# RefOsc10MHz_1V0.net
KiCad netlist of a schematic drawn in EAGLE
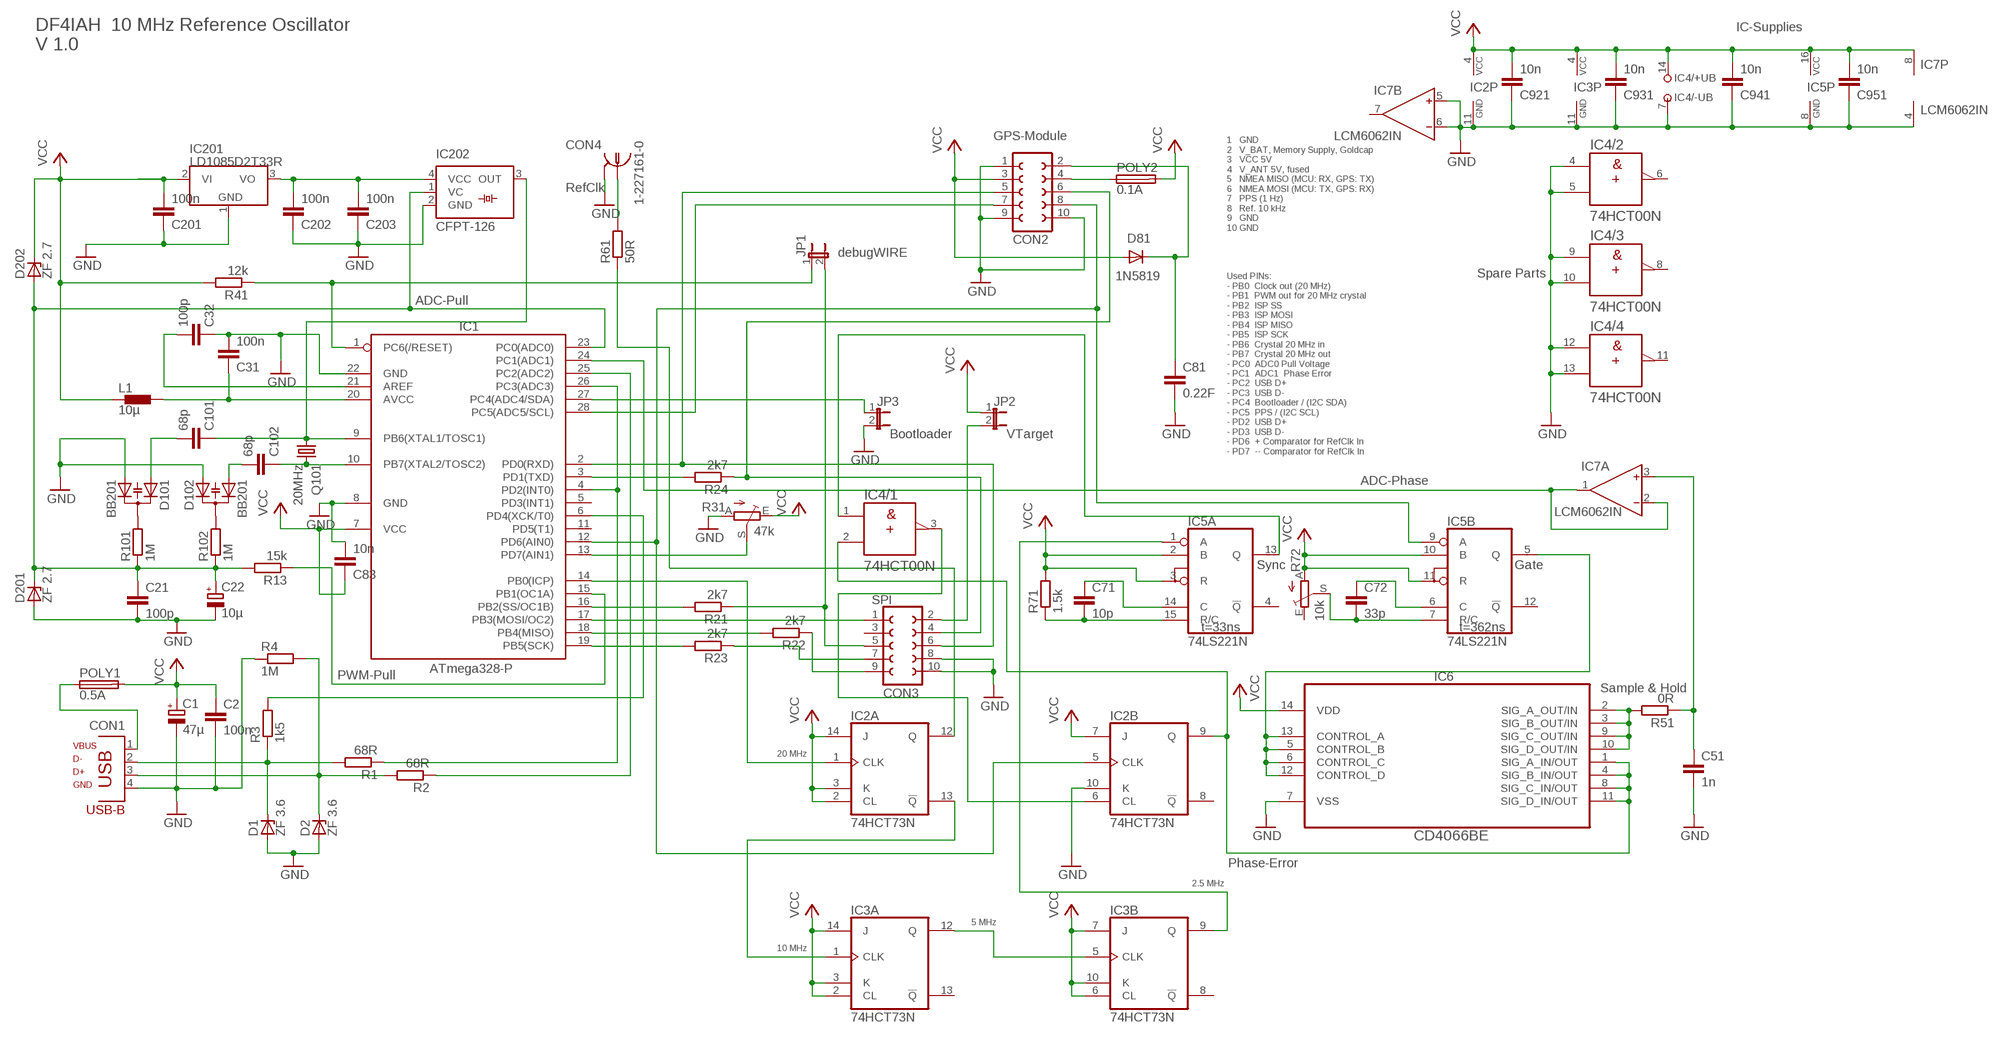
[diagram p0: schematic, sheet 1]

(export (version "E")
  (design (tool "Eeschema 10.0.6"))
  (components
    (comp (ref "C1")
      (value "47µ")
      (footprint "eagle-import:E2-4")
      (libsource (lib "eagle-import") (part "CPOL-EUE2-4"))
    )
    (comp (ref "C2")
      (value "100n")
      (footprint "eagle-import:C5B3")
      (libsource (lib "eagle-import") (part "C5/3"))
    )
    (comp (ref "C21")
      (value "100p")
      (footprint "eagle-import:C5B3")
      (libsource (lib "eagle-import") (part "C5/3"))
    )
    (comp (ref "C22")
      (value "10µ")
      (footprint "eagle-import:E2-4")
      (libsource (lib "eagle-import") (part "CPOL-EUE2-4"))
    )
    (comp (ref "C31")
      (value "100n")
      (footprint "eagle-import:C5B3")
      (libsource (lib "eagle-import") (part "C5/3"))
    )
    (comp (ref "C32")
      (value "100p")
      (footprint "eagle-import:C5B3")
      (libsource (lib "eagle-import") (part "C5/3"))
    )
    (comp (ref "C51")
      (value "1n")
      (footprint "eagle-import:C5B3")
      (libsource (lib "eagle-import") (part "C5/3"))
    )
    (comp (ref "C71")
      (value "10p")
      (footprint "eagle-import:C5B3")
      (libsource (lib "eagle-import") (part "C5/3"))
    )
    (comp (ref "C72")
      (value "33p")
      (footprint "eagle-import:C5B3")
      (libsource (lib "eagle-import") (part "C5/3"))
    )
    (comp (ref "C81")
      (value "0.22F")
      (footprint "eagle-import:C5B7.2")
      (libsource (lib "eagle-import") (part "C5/7.2"))
    )
    (comp (ref "C83")
      (value "10n")
      (footprint "eagle-import:C5B3")
      (libsource (lib "eagle-import") (part "C5/3"))
    )
    (comp (ref "C101")
      (value "68p")
      (footprint "eagle-import:C5B3")
      (libsource (lib "eagle-import") (part "C5/3"))
    )
    (comp (ref "C102")
      (value "68p")
      (footprint "eagle-import:C5B3")
      (libsource (lib "eagle-import") (part "C5/3"))
    )
    (comp (ref "C201")
      (value "100n")
      (footprint "eagle-import:C5B3")
      (libsource (lib "eagle-import") (part "C5/3"))
    )
    (comp (ref "C202")
      (value "100n")
      (footprint "eagle-import:C5B3")
      (libsource (lib "eagle-import") (part "C5/3"))
    )
    (comp (ref "C203")
      (value "100n")
      (footprint "eagle-import:C5B3")
      (libsource (lib "eagle-import") (part "C5/3"))
    )
    (comp (ref "C921")
      (value "10n")
      (footprint "eagle-import:C5B3")
      (libsource (lib "eagle-import") (part "C5/3"))
    )
    (comp (ref "C931")
      (value "10n")
      (footprint "eagle-import:C5B3")
      (libsource (lib "eagle-import") (part "C5/3"))
    )
    (comp (ref "C941")
      (value "10n")
      (footprint "eagle-import:C5B3")
      (libsource (lib "eagle-import") (part "C5/3"))
    )
    (comp (ref "C951")
      (value "10n")
      (footprint "eagle-import:C5B3")
      (libsource (lib "eagle-import") (part "C5/3"))
    )
    (comp (ref "CON1")
      (value "PN61729")
      (footprint "eagle-import:PN61729")
      (libsource (lib "eagle-import") (part "PN61729"))
    )
    (comp (ref "CON2")
      (value "FE05-2")
      (footprint "eagle-import:FE05-2")
      (libsource (lib "eagle-import") (part "FE05-2"))
    )
    (comp (ref "CON3")
      (value "FE05-2")
      (footprint "eagle-import:FE05-2")
      (libsource (lib "eagle-import") (part "FE05-2"))
    )
    (comp (ref "CON4")
      (value "1-227161-0")
      (footprint "eagle-import:AMP_227161")
      (fields (field (name "MF") "TYCO ELECTRONICS") (field (name "MPN") "1-227161"))
      (libsource (lib "eagle-import") (part "?2271611--0"))
    )
    (comp (ref "D1")
      (value "ZF 3.6")
      (footprint "eagle-import:DO41Z10")
      (libsource (lib "eagle-import") (part "1N4728"))
    )
    (comp (ref "D2")
      (value "ZF 3.6")
      (footprint "eagle-import:DO41Z10")
      (libsource (lib "eagle-import") (part "1N4728"))
    )
    (comp (ref "D81")
      (value "1N5819")
      (footprint "eagle-import:DO41-10")
      (libsource (lib "eagle-import") (part "1N4942"))
    )
    (comp (ref "D101")
      (value "BB201")
      (footprint "eagle-import:SOT23")
      (libsource (lib "eagle-import") (part "BBY51"))
    )
    (comp (ref "D102")
      (value "BB201")
      (footprint "eagle-import:SOT23")
      (libsource (lib "eagle-import") (part "BBY51"))
    )
    (comp (ref "D201")
      (value "ZF 2.7")
      (footprint "eagle-import:DO41Z10")
      (libsource (lib "eagle-import") (part "1N4728"))
    )
    (comp (ref "D202")
      (value "ZF 2.7")
      (footprint "eagle-import:DO41Z10")
      (libsource (lib "eagle-import") (part "1N4728"))
    )
    (comp (ref "IC1")
      (value "ATmega328-P")
      (footprint "eagle-import:DIL28-3")
      (libsource (lib "eagle-import") (part "MEGA8-P"))
    )
    (comp (ref "IC2")
      (value "74HCT73N")
      (footprint "eagle-import:DIL14")
      (libsource (lib "eagle-import") (part "7473NLS"))
    )
    (comp (ref "IC3")
      (value "74HCT73N")
      (footprint "eagle-import:DIL14")
      (libsource (lib "eagle-import") (part "7473NLS"))
    )
    (comp (ref "IC4")
      (value "74HCT00N")
      (footprint "eagle-import:DIL14")
      (libsource (lib "eagle-import") (part "7400NHCT"))
    )
    (comp (ref "IC5")
      (value "74LS221N")
      (footprint "eagle-import:DIL16")
      (libsource (lib "eagle-import") (part "74221NLS"))
    )
    (comp (ref "IC6")
      (value "CD4066BE")
      (footprint "eagle-import:DIP254P762X508-14")
      (libsource (lib "eagle-import") (part "CD4066BE"))
    )
    (comp (ref "IC7")
      (value "LCM6062IN")
      (footprint "eagle-import:DIL08")
      (libsource (lib "eagle-import") (part "AD822IN"))
    )
    (comp (ref "IC201")
      (value "LD10853.3")
      (footprint "eagle-import:TO220V")
      (libsource (lib "eagle-import") (part "LD10853.3"))
    )
    (comp (ref "IC202")
      (value "CFPT-126")
      (footprint "eagle-import:SM77H")
      (libsource (lib "eagle-import") (part "CFPT-126"))
    )
    (comp (ref "JP1")
      (value "JP1E")
      (footprint "eagle-import:JP1")
      (libsource (lib "eagle-import") (part "JP1E"))
    )
    (comp (ref "JP2")
      (value "JP1E")
      (footprint "eagle-import:JP1")
      (libsource (lib "eagle-import") (part "JP1E"))
    )
    (comp (ref "JP3")
      (value "JP1E")
      (footprint "eagle-import:JP1")
      (libsource (lib "eagle-import") (part "JP1E"))
    )
    (comp (ref "L1")
      (value "10µ")
      (footprint "eagle-import:BL01RN1A")
      (libsource (lib "eagle-import") (part "BL01RN1A"))
    )
    (comp (ref "POLY1")
      (value "0.5A")
      (footprint "eagle-import:TE5")
      (libsource (lib "eagle-import") (part "FUSETE5"))
    )
    (comp (ref "POLY2")
      (value "0.1A")
      (footprint "eagle-import:TE5")
      (libsource (lib "eagle-import") (part "FUSETE5"))
    )
    (comp (ref "Q101")
      (value "20MHz")
      (footprint "eagle-import:HC49U70")
      (libsource (lib "eagle-import") (part "CRYSTALHC49U70"))
    )
    (comp (ref "R1")
      (value "68R")
      (footprint "eagle-import:0204_7")
      (libsource (lib "eagle-import") (part "R-EU_0204/7"))
    )
    (comp (ref "R2")
      (value "68R")
      (footprint "eagle-import:0204_7")
      (libsource (lib "eagle-import") (part "R-EU_0204/7"))
    )
    (comp (ref "R3")
      (value "1k5")
      (footprint "eagle-import:0204_7")
      (libsource (lib "eagle-import") (part "R-EU_0204/7"))
    )
    (comp (ref "R4")
      (value "1M")
      (footprint "eagle-import:0204_7")
      (libsource (lib "eagle-import") (part "R-EU_0204/7"))
    )
    (comp (ref "R13")
      (value "15k")
      (footprint "eagle-import:0204_7")
      (libsource (lib "eagle-import") (part "R-EU_0204/7"))
    )
    (comp (ref "R21")
      (value "2k7")
      (footprint "eagle-import:0204_7")
      (libsource (lib "eagle-import") (part "R-EU_0204/7"))
    )
    (comp (ref "R22")
      (value "2k7")
      (footprint "eagle-import:0204_7")
      (libsource (lib "eagle-import") (part "R-EU_0204/7"))
    )
    (comp (ref "R23")
      (value "2k7")
      (footprint "eagle-import:0204_7")
      (libsource (lib "eagle-import") (part "R-EU_0204/7"))
    )
    (comp (ref "R24")
      (value "2k7")
      (footprint "eagle-import:0204_7")
      (libsource (lib "eagle-import") (part "R-EU_0204/7"))
    )
    (comp (ref "R31")
      (value "47k")
      (footprint "eagle-import:S64YW")
      (libsource (lib "eagle-import") (part "TRIM_1234-S64YW"))
    )
    (comp (ref "R41")
      (value "12k")
      (footprint "eagle-import:0204_7")
      (libsource (lib "eagle-import") (part "R-EU_0204/7"))
    )
    (comp (ref "R51")
      (value "0R")
      (footprint "eagle-import:0204_7")
      (libsource (lib "eagle-import") (part "R-EU_0204/7"))
    )
    (comp (ref "R61")
      (value "50R")
      (footprint "eagle-import:0204_7")
      (libsource (lib "eagle-import") (part "R-EU_0204/7"))
    )
    (comp (ref "R71")
      (value "1.5k")
      (footprint "eagle-import:0204_7")
      (libsource (lib "eagle-import") (part "R-EU_0204/7"))
    )
    (comp (ref "R72")
      (value "10k")
      (footprint "eagle-import:S64YW")
      (libsource (lib "eagle-import") (part "TRIM_1234-S64YW"))
    )
    (comp (ref "R101")
      (value "1M")
      (footprint "eagle-import:0204_7")
      (libsource (lib "eagle-import") (part "R-EU_0204/7"))
    )
    (comp (ref "R102")
      (value "1M")
      (footprint "eagle-import:0204_7")
      (libsource (lib "eagle-import") (part "R-EU_0204/7"))
    )
  )
  (nets
    (net (code "1") (name "GND") (class "Default")
      (node (ref "C1") (pin "-") (pinfunction "-_-") (pintype "passive"))
      (node (ref "C2") (pin "2") (pinfunction "2_2") (pintype "passive"))
      (node (ref "C201") (pin "1") (pinfunction "1_1") (pintype "passive"))
      (node (ref "C202") (pin "1") (pinfunction "1_1") (pintype "passive"))
      (node (ref "C203") (pin "1") (pinfunction "1_1") (pintype "passive"))
      (node (ref "C21") (pin "2") (pinfunction "2_2") (pintype "passive"))
      (node (ref "C22") (pin "-") (pinfunction "-_-") (pintype "passive"))
      (node (ref "C31") (pin "2") (pinfunction "2_2") (pintype "passive"))
      (node (ref "C32") (pin "1") (pinfunction "1_1") (pintype "passive"))
      (node (ref "C51") (pin "2") (pinfunction "2_2") (pintype "passive"))
      (node (ref "C81") (pin "2") (pinfunction "2_2") (pintype "passive"))
      (node (ref "C83") (pin "2") (pinfunction "2_2") (pintype "passive"))
      (node (ref "C921") (pin "1") (pinfunction "1_1") (pintype "passive"))
      (node (ref "C931") (pin "1") (pinfunction "1_1") (pintype "passive"))
      (node (ref "C941") (pin "1") (pinfunction "1_1") (pintype "passive"))
      (node (ref "C951") (pin "1") (pinfunction "1_1") (pintype "passive"))
      (node (ref "CON1") (pin "4") (pinfunction "4_4") (pintype "passive"))
      (node (ref "CON2") (pin "1") (pinfunction "1_1") (pintype "passive"))
      (node (ref "CON2") (pin "10") (pinfunction "10_10") (pintype "passive"))
      (node (ref "CON2") (pin "9") (pinfunction "9_9") (pintype "passive"))
      (node (ref "CON3") (pin "10") (pinfunction "10_10") (pintype "passive"))
      (node (ref "CON3") (pin "8") (pinfunction "8_8") (pintype "passive"))
      (node (ref "CON4") (pin "2") (pinfunction "2_2") (pintype "passive"))
      (node (ref "D1") (pin "A") (pinfunction "A_A") (pintype "passive"))
      (node (ref "D101") (pin "2") (pinfunction "A2_2") (pintype "passive"))
      (node (ref "D102") (pin "1") (pinfunction "A1_1") (pintype "passive"))
      (node (ref "D2") (pin "A") (pinfunction "A_A") (pintype "passive"))
      (node (ref "D201") (pin "A") (pinfunction "A_A") (pintype "passive"))
      (node (ref "IC1") (pin "22") (pinfunction "GND_22") (pintype "power_in"))
      (node (ref "IC1") (pin "8") (pinfunction "GND_8") (pintype "power_in"))
      (node (ref "IC2") (pin "10") (pinfunction "K_10") (pintype "input"))
      (node (ref "IC2") (pin "11") (pinfunction "GND_11") (pintype "power_in"))
      (node (ref "IC201") (pin "1") (pinfunction "GND_1") (pintype "passive"))
      (node (ref "IC202") (pin "2") (pinfunction "GND_2") (pintype "power_in"))
      (node (ref "IC3") (pin "11") (pinfunction "GND_11") (pintype "power_in"))
      (node (ref "IC4") (pin "10") (pinfunction "B_10") (pintype "input"))
      (node (ref "IC4") (pin "12") (pinfunction "A_12") (pintype "input"))
      (node (ref "IC4") (pin "13") (pinfunction "B_13") (pintype "input"))
      (node (ref "IC4") (pin "4") (pinfunction "A_4") (pintype "input"))
      (node (ref "IC4") (pin "5") (pinfunction "B_5") (pintype "input"))
      (node (ref "IC4") (pin "7") (pinfunction "-UB_7") (pintype "power_in"))
      (node (ref "IC4") (pin "9") (pinfunction "A_9") (pintype "input"))
      (node (ref "IC5") (pin "8") (pinfunction "GND_8") (pintype "power_in"))
      (node (ref "IC6") (pin "7") (pinfunction "VSS_7") (pintype "passive"))
      (node (ref "IC7") (pin "4") (pinfunction "V-_4") (pintype "power_in"))
      (node (ref "IC7") (pin "5") (pinfunction "IN+_5") (pintype "input"))
      (node (ref "IC7") (pin "6") (pinfunction "IN-_6") (pintype "input"))
      (node (ref "JP3") (pin "2") (pinfunction "2_2") (pintype "passive"))
      (node (ref "R31") (pin "A") (pinfunction "A_A") (pintype "passive"))
      (node (ref "R4") (pin "1") (pinfunction "1_1") (pintype "passive"))
    )
    (net (code "2") (name "Net-(C81-Pad1)") (class "Default")
      (node (ref "C81") (pin "1") (pinfunction "1_1") (pintype "passive"))
      (node (ref "CON2") (pin "2") (pinfunction "2_2") (pintype "passive"))
      (node (ref "D81") (pin "C") (pinfunction "C_C") (pintype "passive"))
    )
    (net (code "3") (name "Net-(CON1-Pad1)") (class "Default")
      (node (ref "CON1") (pin "1") (pinfunction "1_1") (pintype "passive"))
      (node (ref "POLY1") (pin "1") (pinfunction "1_1") (pintype "passive"))
    )
    (net (code "4") (name "Net-(CON1-Pad2)") (class "Default")
      (node (ref "CON1") (pin "2") (pinfunction "2_2") (pintype "passive"))
      (node (ref "D1") (pin "C") (pinfunction "C_C") (pintype "passive"))
      (node (ref "R1") (pin "2") (pinfunction "2_2") (pintype "passive"))
      (node (ref "R3") (pin "1") (pinfunction "1_1") (pintype "passive"))
    )
    (net (code "5") (name "Net-(CON1-Pad3)") (class "Default")
      (node (ref "CON1") (pin "3") (pinfunction "3_3") (pintype "passive"))
      (node (ref "D2") (pin "C") (pinfunction "C_C") (pintype "passive"))
      (node (ref "R2") (pin "2") (pinfunction "2_2") (pintype "passive"))
      (node (ref "R4") (pin "2") (pinfunction "2_2") (pintype "passive"))
    )
    (net (code "6") (name "Net-(CON2-Pad4)") (class "Default")
      (node (ref "CON2") (pin "4") (pinfunction "4_4") (pintype "passive"))
      (node (ref "POLY2") (pin "1") (pinfunction "1_1") (pintype "passive"))
    )
    (net (code "7") (name "Net-(CON2-Pad6)") (class "Default")
      (node (ref "CON2") (pin "6") (pinfunction "6_6") (pintype "passive"))
      (node (ref "CON3") (pin "4") (pinfunction "4_4") (pintype "passive"))
      (node (ref "R24") (pin "1") (pinfunction "1_1") (pintype "passive"))
    )
    (net (code "8") (name "Net-(CON3-Pad2)") (class "Default")
      (node (ref "CON3") (pin "2") (pinfunction "2_2") (pintype "passive"))
      (node (ref "JP2") (pin "2") (pinfunction "2_2") (pintype "passive"))
    )
    (net (code "9") (name "Net-(CON3-Pad5)") (class "Default")
      (node (ref "CON3") (pin "5") (pinfunction "5_5") (pintype "passive"))
      (node (ref "JP1") (pin "2") (pinfunction "2_2") (pintype "passive"))
      (node (ref "R21") (pin "1") (pinfunction "1_1") (pintype "passive"))
    )
    (net (code "10") (name "Net-(CON3-Pad7)") (class "Default")
      (node (ref "CON3") (pin "7") (pinfunction "7_7") (pintype "passive"))
      (node (ref "R23") (pin "1") (pinfunction "1_1") (pintype "passive"))
    )
    (net (code "11") (name "Net-(CON3-Pad9)") (class "Default")
      (node (ref "CON3") (pin "9") (pinfunction "9_9") (pintype "passive"))
      (node (ref "R22") (pin "1") (pinfunction "1_1") (pintype "passive"))
    )
    (net (code "12") (name "Net-(CON4-Pad1)") (class "Default")
      (node (ref "CON4") (pin "1") (pinfunction "1_1") (pintype "passive"))
      (node (ref "R61") (pin "2") (pinfunction "2_2") (pintype "passive"))
    )
    (net (code "13") (name "Net-(D101-A1)") (class "Default")
      (node (ref "C101") (pin "2") (pinfunction "2_2") (pintype "passive"))
      (node (ref "D101") (pin "1") (pinfunction "A1_1") (pintype "passive"))
    )
    (net (code "14") (name "Net-(D101-C)") (class "Default")
      (node (ref "D101") (pin "3") (pinfunction "C_3") (pintype "passive"))
      (node (ref "R101") (pin "2") (pinfunction "2_2") (pintype "passive"))
    )
    (net (code "15") (name "Net-(D102-A2)") (class "Default")
      (node (ref "C102") (pin "2") (pinfunction "2_2") (pintype "passive"))
      (node (ref "D102") (pin "2") (pinfunction "A2_2") (pintype "passive"))
    )
    (net (code "16") (name "Net-(D102-C)") (class "Default")
      (node (ref "D102") (pin "3") (pinfunction "C_3") (pintype "passive"))
      (node (ref "R102") (pin "2") (pinfunction "2_2") (pintype "passive"))
    )
    (net (code "17") (name "Net-(IC1-AREF)") (class "Default")
      (node (ref "C32") (pin "2") (pinfunction "2_2") (pintype "passive"))
      (node (ref "IC1") (pin "21") (pinfunction "AREF_21") (pintype "passive"))
    )
    (net (code "18") (name "Net-(IC1-AVCC)") (class "Default")
      (node (ref "C31") (pin "1") (pinfunction "1_1") (pintype "passive"))
      (node (ref "IC1") (pin "20") (pinfunction "AVCC_20") (pintype "power_in"))
      (node (ref "L1") (pin "2") (pinfunction "2_2") (pintype "passive"))
    )
    (net (code "19") (name "Net-(IC1-PB0(ICP))") (class "Default")
      (node (ref "IC1") (pin "14") (pinfunction "PB0(ICP)_14") (pintype "bidirectional"))
      (node (ref "IC2") (pin "1") (pinfunction "CLK_1") (pintype "input"))
    )
    (net (code "20") (name "Net-(IC1-PB1(OC1A))") (class "Default")
      (node (ref "IC1") (pin "15") (pinfunction "PB1(OC1A)_15") (pintype "bidirectional"))
      (node (ref "R13") (pin "1") (pinfunction "1_1") (pintype "passive"))
    )
    (net (code "21") (name "Net-(IC1-PB2(SS{slash}OC1B))") (class "Default")
      (node (ref "IC1") (pin "16") (pinfunction "PB2(SS/OC1B)_16") (pintype "bidirectional"))
      (node (ref "R21") (pin "2") (pinfunction "2_2") (pintype "passive"))
    )
    (net (code "22") (name "Net-(IC1-PB3(MOSI{slash}OC2))") (class "Default")
      (node (ref "CON3") (pin "1") (pinfunction "1_1") (pintype "passive"))
      (node (ref "IC1") (pin "17") (pinfunction "PB3(MOSI/OC2)_17") (pintype "bidirectional"))
    )
    (net (code "23") (name "Net-(IC1-PB4(MISO))") (class "Default")
      (node (ref "IC1") (pin "18") (pinfunction "PB4(MISO)_18") (pintype "bidirectional"))
      (node (ref "R22") (pin "2") (pinfunction "2_2") (pintype "passive"))
    )
    (net (code "24") (name "Net-(IC1-PB5(SCK))") (class "Default")
      (node (ref "IC1") (pin "19") (pinfunction "PB5(SCK)_19") (pintype "bidirectional"))
      (node (ref "R23") (pin "2") (pinfunction "2_2") (pintype "passive"))
    )
    (net (code "25") (name "Net-(IC1-PB6(XTAL1{slash}TOSC1))") (class "Default")
      (node (ref "C101") (pin "1") (pinfunction "1_1") (pintype "passive"))
      (node (ref "IC1") (pin "9") (pinfunction "PB6(XTAL1/TOSC1)_9") (pintype "bidirectional"))
      (node (ref "IC202") (pin "3") (pinfunction "OUT_3") (pintype "output"))
      (node (ref "Q101") (pin "1") (pinfunction "1_1") (pintype "passive"))
    )
    (net (code "26") (name "Net-(IC1-PB7(XTAL2{slash}TOSC2))") (class "Default")
      (node (ref "C102") (pin "1") (pinfunction "1_1") (pintype "passive"))
      (node (ref "IC1") (pin "10") (pinfunction "PB7(XTAL2/TOSC2)_10") (pintype "bidirectional"))
      (node (ref "Q101") (pin "2") (pinfunction "2_2") (pintype "passive"))
    )
    (net (code "27") (name "Net-(IC1-PC0(ADC0))") (class "Default")
      (node (ref "C21") (pin "1") (pinfunction "1_1") (pintype "passive"))
      (node (ref "C22") (pin "+") (pinfunction "+_+") (pintype "passive"))
      (node (ref "D201") (pin "C") (pinfunction "C_C") (pintype "passive"))
      (node (ref "D202") (pin "A") (pinfunction "A_A") (pintype "passive"))
      (node (ref "IC1") (pin "23") (pinfunction "PC0(ADC0)_23") (pintype "bidirectional"))
      (node (ref "IC202") (pin "1") (pinfunction "VC_1") (pintype "input"))
      (node (ref "R101") (pin "1") (pinfunction "1_1") (pintype "passive"))
      (node (ref "R102") (pin "1") (pinfunction "1_1") (pintype "passive"))
      (node (ref "R13") (pin "2") (pinfunction "2_2") (pintype "passive"))
    )
    (net (code "28") (name "Net-(IC1-PC1(ADC1))") (class "Default")
      (node (ref "IC1") (pin "24") (pinfunction "PC1(ADC1)_24") (pintype "bidirectional"))
      (node (ref "IC7") (pin "1") (pinfunction "OUT_1") (pintype "output"))
      (node (ref "IC7") (pin "2") (pinfunction "IN-_2") (pintype "input"))
    )
    (net (code "29") (name "Net-(IC1-PC2(ADC2))") (class "Default")
      (node (ref "IC1") (pin "25") (pinfunction "PC2(ADC2)_25") (pintype "bidirectional"))
      (node (ref "R2") (pin "1") (pinfunction "1_1") (pintype "passive"))
    )
    (net (code "30") (name "Net-(IC1-PC3(ADC3))") (class "Default")
      (node (ref "IC1") (pin "26") (pinfunction "PC3(ADC3)_26") (pintype "bidirectional"))
      (node (ref "IC1") (pin "4") (pinfunction "PD2(INT0)_4") (pintype "bidirectional"))
      (node (ref "R1") (pin "1") (pinfunction "1_1") (pintype "passive"))
    )
    (net (code "31") (name "Net-(IC1-PC4(ADC4{slash}SDA))") (class "Default")
      (node (ref "IC1") (pin "27") (pinfunction "PC4(ADC4/SDA)_27") (pintype "bidirectional"))
      (node (ref "JP3") (pin "1") (pinfunction "1_1") (pintype "passive"))
    )
    (net (code "32") (name "Net-(IC1-PC5(ADC5{slash}SCL))") (class "Default")
      (node (ref "CON2") (pin "7") (pinfunction "7_7") (pintype "passive"))
      (node (ref "IC1") (pin "28") (pinfunction "PC5(ADC5/SCL)_28") (pintype "bidirectional"))
    )
    (net (code "33") (name "Net-(IC1-PC6({slash}RESET))") (class "Default")
      (node (ref "IC1") (pin "1") (pinfunction "PC6(/RESET)_1") (pintype "bidirectional"))
      (node (ref "JP1") (pin "1") (pinfunction "1_1") (pintype "passive"))
      (node (ref "R41") (pin "1") (pinfunction "1_1") (pintype "passive"))
    )
    (net (code "34") (name "Net-(IC1-PD0(RXD))") (class "Default")
      (node (ref "CON2") (pin "5") (pinfunction "5_5") (pintype "passive"))
      (node (ref "CON3") (pin "6") (pinfunction "6_6") (pintype "passive"))
      (node (ref "IC1") (pin "2") (pinfunction "PD0(RXD)_2") (pintype "bidirectional"))
    )
    (net (code "35") (name "Net-(IC1-PD1(TXD))") (class "Default")
      (node (ref "IC1") (pin "3") (pinfunction "PD1(TXD)_3") (pintype "bidirectional"))
      (node (ref "R24") (pin "2") (pinfunction "2_2") (pintype "passive"))
    )
    (net (code "36") (name "Net-(IC1-PD4(XCK{slash}T0))") (class "Default")
      (node (ref "IC1") (pin "6") (pinfunction "PD4(XCK/T0)_6") (pintype "bidirectional"))
      (node (ref "R3") (pin "2") (pinfunction "2_2") (pintype "passive"))
    )
    (net (code "37") (name "Net-(IC1-PD6(AIN0))") (class "Default")
      (node (ref "CON2") (pin "8") (pinfunction "8_8") (pintype "passive"))
      (node (ref "IC1") (pin "12") (pinfunction "PD6(AIN0)_12") (pintype "bidirectional"))
      (node (ref "IC2") (pin "5") (pinfunction "CLK_5") (pintype "input"))
      (node (ref "IC5") (pin "9") (pinfunction "A_9") (pintype "input"))
    )
    (net (code "38") (name "Net-(IC1-PD7(AIN1))") (class "Default")
      (node (ref "IC1") (pin "13") (pinfunction "PD7(AIN1)_13") (pintype "bidirectional"))
      (node (ref "R31") (pin "S") (pinfunction "S_S") (pintype "passive"))
    )
    (net (code "39") (name "Net-(IC2A-Q)") (class "Default")
      (node (ref "IC2") (pin "12") (pinfunction "Q_12") (pintype "output"))
      (node (ref "R61") (pin "1") (pinfunction "1_1") (pintype "passive"))
    )
    (net (code "40") (name "Net-(IC2A-~{Q})") (class "Default")
      (node (ref "IC2") (pin "13") (pinfunction "~{Q}_13") (pintype "output"))
      (node (ref "IC3") (pin "1") (pinfunction "CLK_1") (pintype "input"))
    )
    (net (code "41") (name "Net-(IC2B-CL)") (class "Default")
      (node (ref "IC2") (pin "6") (pinfunction "CL_6") (pintype "input"))
      (node (ref "IC4") (pin "3") (pinfunction "Y_3") (pintype "output"))
    )
    (net (code "42") (name "Net-(IC2B-Q)") (class "Default")
      (node (ref "IC2") (pin "9") (pinfunction "Q_9") (pintype "output"))
      (node (ref "IC4") (pin "2") (pinfunction "B_2") (pintype "input"))
      (node (ref "IC6") (pin "1") (pinfunction "SIG_A_IN/OUT_1") (pintype "bidirectional"))
      (node (ref "IC6") (pin "11") (pinfunction "SIG_D_IN/OUT_11") (pintype "bidirectional"))
      (node (ref "IC6") (pin "4") (pinfunction "SIG_B_IN/OUT_4") (pintype "bidirectional"))
      (node (ref "IC6") (pin "8") (pinfunction "SIG_C_IN/OUT_8") (pintype "bidirectional"))
    )
    (net (code "43") (name "Net-(IC3A-Q)") (class "Default")
      (node (ref "IC3") (pin "12") (pinfunction "Q_12") (pintype "output"))
      (node (ref "IC3") (pin "5") (pinfunction "CLK_5") (pintype "input"))
    )
    (net (code "44") (name "Net-(IC3B-Q)") (class "Default")
      (node (ref "IC3") (pin "9") (pinfunction "Q_9") (pintype "output"))
      (node (ref "IC5") (pin "1") (pinfunction "A_1") (pintype "input"))
    )
    (net (code "45") (name "Net-(IC4C-A)") (class "Default")
      (node (ref "IC4") (pin "1") (pinfunction "A_1") (pintype "input"))
      (node (ref "IC5") (pin "13") (pinfunction "Q_13") (pintype "output"))
    )
    (net (code "46") (name "Net-(IC5A-C)") (class "Default")
      (node (ref "C71") (pin "1") (pinfunction "1_1") (pintype "passive"))
      (node (ref "IC5") (pin "14") (pinfunction "C_14") (pintype "input"))
    )
    (net (code "47") (name "Net-(IC5A-R{slash}C)") (class "Default")
      (node (ref "C71") (pin "2") (pinfunction "2_2") (pintype "passive"))
      (node (ref "IC5") (pin "15") (pinfunction "R/C_15") (pintype "input"))
      (node (ref "R71") (pin "1") (pinfunction "1_1") (pintype "passive"))
    )
    (net (code "48") (name "Net-(IC5B-C)") (class "Default")
      (node (ref "C72") (pin "1") (pinfunction "1_1") (pintype "passive"))
      (node (ref "IC5") (pin "6") (pinfunction "C_6") (pintype "input"))
    )
    (net (code "49") (name "Net-(IC5B-Q)") (class "Default")
      (node (ref "IC5") (pin "5") (pinfunction "Q_5") (pintype "output"))
      (node (ref "IC6") (pin "12") (pinfunction "CONTROL_D_12") (pintype "input"))
      (node (ref "IC6") (pin "13") (pinfunction "CONTROL_A_13") (pintype "input"))
      (node (ref "IC6") (pin "5") (pinfunction "CONTROL_B_5") (pintype "input"))
      (node (ref "IC6") (pin "6") (pinfunction "CONTROL_C_6") (pintype "input"))
    )
    (net (code "50") (name "Net-(IC5B-R{slash}C)") (class "Default")
      (node (ref "C72") (pin "2") (pinfunction "2_2") (pintype "passive"))
      (node (ref "IC5") (pin "7") (pinfunction "R/C_7") (pintype "input"))
      (node (ref "R72") (pin "S") (pinfunction "S_S") (pintype "passive"))
    )
    (net (code "51") (name "Net-(IC6-SIG_A_OUT{slash}IN)") (class "Default")
      (node (ref "IC6") (pin "10") (pinfunction "SIG_D_OUT/IN_10") (pintype "bidirectional"))
      (node (ref "IC6") (pin "2") (pinfunction "SIG_A_OUT/IN_2") (pintype "bidirectional"))
      (node (ref "IC6") (pin "3") (pinfunction "SIG_B_OUT/IN_3") (pintype "bidirectional"))
      (node (ref "IC6") (pin "9") (pinfunction "SIG_C_OUT/IN_9") (pintype "bidirectional"))
      (node (ref "R51") (pin "2") (pinfunction "2_2") (pintype "passive"))
    )
    (net (code "52") (name "Net-(IC7A-IN+)") (class "Default")
      (node (ref "C51") (pin "1") (pinfunction "1_1") (pintype "passive"))
      (node (ref "IC7") (pin "3") (pinfunction "IN+_3") (pintype "input"))
      (node (ref "R51") (pin "1") (pinfunction "1_1") (pintype "passive"))
    )
    (net (code "53") (name "Net-(IC201-VO)") (class "Default")
      (node (ref "C202") (pin "2") (pinfunction "2_2") (pintype "passive"))
      (node (ref "C203") (pin "2") (pinfunction "2_2") (pintype "passive"))
      (node (ref "IC201") (pin "3") (pinfunction "VO_3") (pintype "passive"))
      (node (ref "IC202") (pin "4") (pinfunction "VCC_4") (pintype "power_in"))
    )
    (net (code "54") (name "VCC") (class "Default")
      (node (ref "C1") (pin "+") (pinfunction "+_+") (pintype "passive"))
      (node (ref "C2") (pin "1") (pinfunction "1_1") (pintype "passive"))
      (node (ref "C201") (pin "2") (pinfunction "2_2") (pintype "passive"))
      (node (ref "C83") (pin "1") (pinfunction "1_1") (pintype "passive"))
      (node (ref "C921") (pin "2") (pinfunction "2_2") (pintype "passive"))
      (node (ref "C931") (pin "2") (pinfunction "2_2") (pintype "passive"))
      (node (ref "C941") (pin "2") (pinfunction "2_2") (pintype "passive"))
      (node (ref "C951") (pin "2") (pinfunction "2_2") (pintype "passive"))
      (node (ref "CON2") (pin "3") (pinfunction "3_3") (pintype "passive"))
      (node (ref "D202") (pin "C") (pinfunction "C_C") (pintype "passive"))
      (node (ref "D81") (pin "A") (pinfunction "A_A") (pintype "passive"))
      (node (ref "IC1") (pin "7") (pinfunction "VCC_7") (pintype "power_in"))
      (node (ref "IC2") (pin "14") (pinfunction "J_14") (pintype "input"))
      (node (ref "IC2") (pin "2") (pinfunction "CL_2") (pintype "input"))
      (node (ref "IC2") (pin "3") (pinfunction "K_3") (pintype "input"))
      (node (ref "IC2") (pin "4") (pinfunction "VCC_4") (pintype "power_in"))
      (node (ref "IC2") (pin "7") (pinfunction "J_7") (pintype "input"))
      (node (ref "IC201") (pin "2") (pinfunction "VI_2") (pintype "input"))
      (node (ref "IC3") (pin "10") (pinfunction "K_10") (pintype "input"))
      (node (ref "IC3") (pin "14") (pinfunction "J_14") (pintype "input"))
      (node (ref "IC3") (pin "2") (pinfunction "CL_2") (pintype "input"))
      (node (ref "IC3") (pin "3") (pinfunction "K_3") (pintype "input"))
      (node (ref "IC3") (pin "4") (pinfunction "VCC_4") (pintype "power_in"))
      (node (ref "IC3") (pin "6") (pinfunction "CL_6") (pintype "input"))
      (node (ref "IC3") (pin "7") (pinfunction "J_7") (pintype "input"))
      (node (ref "IC4") (pin "14") (pinfunction "+UB_14") (pintype "power_in"))
      (node (ref "IC5") (pin "10") (pinfunction "B_10") (pintype "input"))
      (node (ref "IC5") (pin "11") (pinfunction "R_11") (pintype "input"))
      (node (ref "IC5") (pin "16") (pinfunction "VCC_16") (pintype "power_in"))
      (node (ref "IC5") (pin "2") (pinfunction "B_2") (pintype "input"))
      (node (ref "IC5") (pin "3") (pinfunction "R_3") (pintype "input"))
      (node (ref "IC6") (pin "14") (pinfunction "VDD_14") (pintype "power_in"))
      (node (ref "IC7") (pin "8") (pinfunction "V+_8") (pintype "power_in"))
      (node (ref "JP2") (pin "1") (pinfunction "1_1") (pintype "passive"))
      (node (ref "L1") (pin "1") (pinfunction "1_1") (pintype "passive"))
      (node (ref "POLY1") (pin "2") (pinfunction "2_2") (pintype "passive"))
      (node (ref "POLY2") (pin "2") (pinfunction "2_2") (pintype "passive"))
      (node (ref "R31") (pin "E") (pinfunction "E_E") (pintype "passive"))
      (node (ref "R41") (pin "2") (pinfunction "2_2") (pintype "passive"))
      (node (ref "R71") (pin "2") (pinfunction "2_2") (pintype "passive"))
      (node (ref "R72") (pin "A") (pinfunction "A_A") (pintype "passive"))
    )
    (net (code "55") (name "unconnected-(CON3-Pad3)") (class "Default")
      (node (ref "CON3") (pin "3") (pinfunction "3_3") (pintype "passive"))
    )
    (net (code "56") (name "unconnected-(IC1-PD3(INT1)-Pad5)") (class "Default")
      (node (ref "IC1") (pin "5") (pinfunction "PD3(INT1)_5") (pintype "bidirectional"))
    )
    (net (code "57") (name "unconnected-(IC1-PD5(T1)-Pad11)") (class "Default")
      (node (ref "IC1") (pin "11") (pinfunction "PD5(T1)_11") (pintype "bidirectional"))
    )
    (net (code "58") (name "unconnected-(IC2B-~{Q}-Pad8)") (class "Default")
      (node (ref "IC2") (pin "8") (pinfunction "~{Q}_8") (pintype "output"))
    )
    (net (code "59") (name "unconnected-(IC3A-~{Q}-Pad13)") (class "Default")
      (node (ref "IC3") (pin "13") (pinfunction "~{Q}_13") (pintype "output"))
    )
    (net (code "60") (name "unconnected-(IC3B-~{Q}-Pad8)") (class "Default")
      (node (ref "IC3") (pin "8") (pinfunction "~{Q}_8") (pintype "output"))
    )
    (net (code "61") (name "unconnected-(IC4D-Y-Pad6)") (class "Default")
      (node (ref "IC4") (pin "6") (pinfunction "Y_6") (pintype "output"))
    )
    (net (code "62") (name "unconnected-(IC4E-Y-Pad8)") (class "Default")
      (node (ref "IC4") (pin "8") (pinfunction "Y_8") (pintype "output"))
    )
    (net (code "63") (name "unconnected-(IC4F-Y-Pad11)") (class "Default")
      (node (ref "IC4") (pin "11") (pinfunction "Y_11") (pintype "output"))
    )
    (net (code "64") (name "unconnected-(IC5A-~{Q}-Pad4)") (class "Default")
      (node (ref "IC5") (pin "4") (pinfunction "~{Q}_4") (pintype "output"))
    )
    (net (code "65") (name "unconnected-(IC5B-~{Q}-Pad12)") (class "Default")
      (node (ref "IC5") (pin "12") (pinfunction "~{Q}_12") (pintype "output"))
    )
    (net (code "66") (name "unconnected-(IC7B-OUT-Pad7)") (class "Default")
      (node (ref "IC7") (pin "7") (pinfunction "OUT_7") (pintype "output"))
    )
    (net (code "67") (name "unconnected-(R31-S-PadS@1)") (class "Default")
      (node (ref "R31") (pin "S@1") (pinfunction "S_S@1") (pintype "passive"))
    )
    (net (code "68") (name "unconnected-(R72-PadE)") (class "Default")
      (node (ref "R72") (pin "E") (pinfunction "E_E") (pintype "passive"))
    )
    (net (code "69") (name "unconnected-(R72-S-PadS@1)") (class "Default")
      (node (ref "R72") (pin "S@1") (pinfunction "S_S@1") (pintype "passive"))
    )
  )
)
